# sensor_node.net
KiCad netlist of a schematic drawn in EAGLE
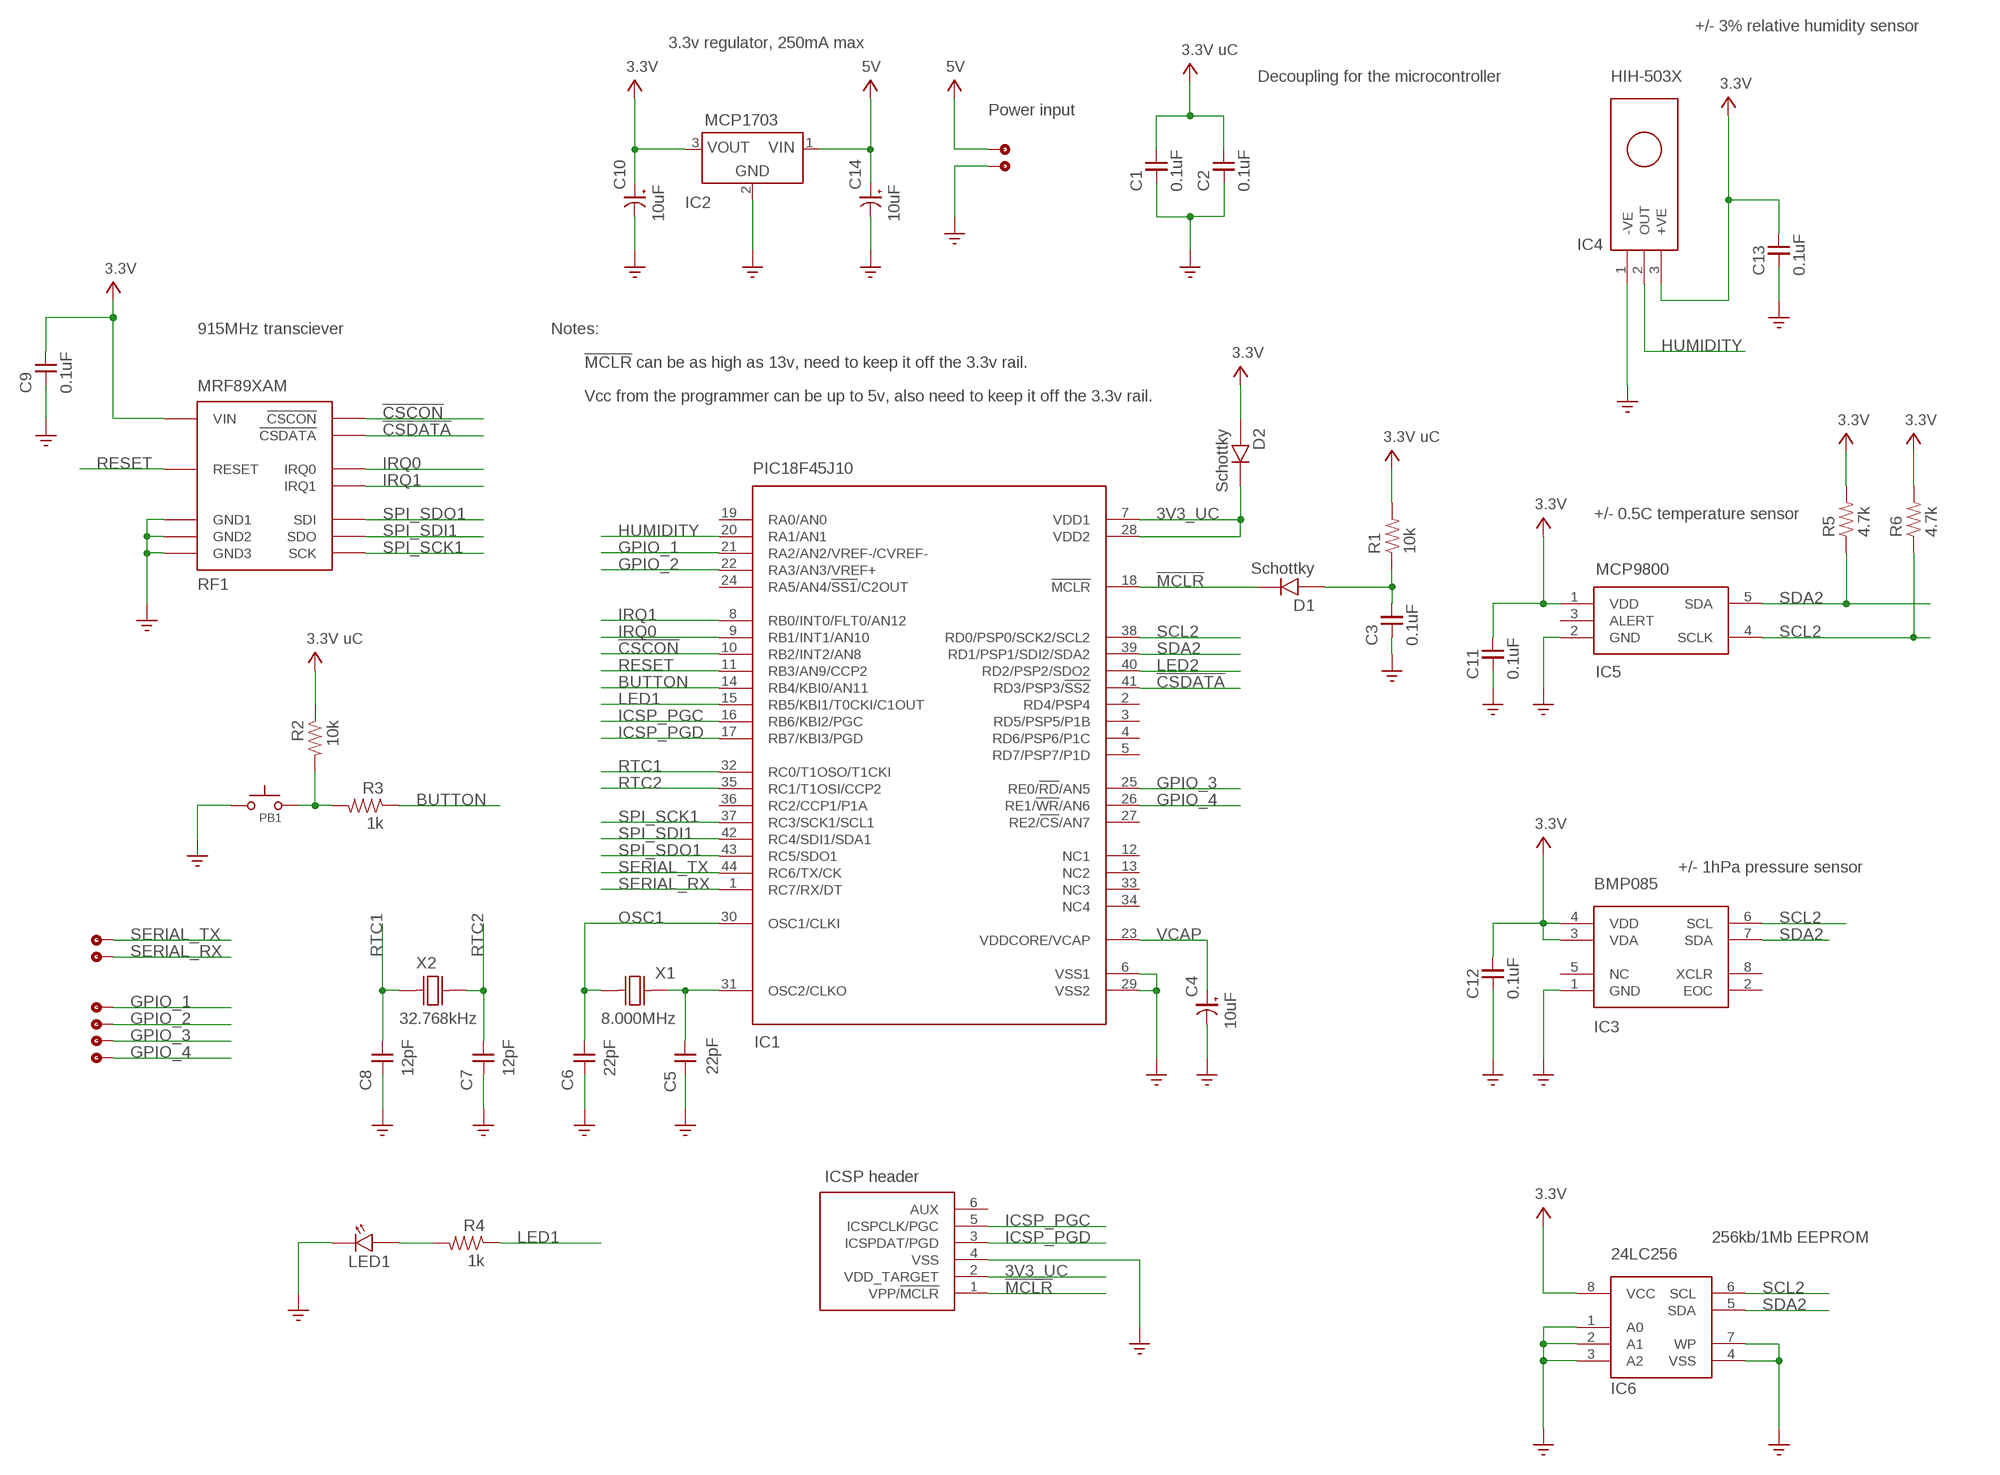
[diagram p0: schematic, sheet 1]

(export (version "E")
  (design (tool "Eeschema 10.0.6"))
  (components
    (comp (ref "C1")
      (value "0.1uF")
      (footprint "eagle-import:0805")
      (libsource (lib "eagle-import") (part "CAPACITOR0805"))
    )
    (comp (ref "C2")
      (value "0.1uF")
      (footprint "eagle-import:0805")
      (libsource (lib "eagle-import") (part "CAPACITOR0805"))
    )
    (comp (ref "C3")
      (value "0.1uF")
      (footprint "eagle-import:0805")
      (libsource (lib "eagle-import") (part "CAPACITOR0805"))
    )
    (comp (ref "C4")
      (value "10uF")
      (footprint "eagle-import:1206")
      (libsource (lib "eagle-import") (part "thomas_july_29_2013_CAPACITOR+"))
    )
    (comp (ref "C5")
      (value "22pF")
      (footprint "eagle-import:0805")
      (libsource (lib "eagle-import") (part "CAPACITOR0805"))
    )
    (comp (ref "C6")
      (value "22pF")
      (footprint "eagle-import:0805")
      (libsource (lib "eagle-import") (part "CAPACITOR0805"))
    )
    (comp (ref "C7")
      (value "12pF")
      (footprint "eagle-import:0805")
      (libsource (lib "eagle-import") (part "CAPACITOR0805"))
    )
    (comp (ref "C8")
      (value "12pF")
      (footprint "eagle-import:0805")
      (libsource (lib "eagle-import") (part "CAPACITOR0805"))
    )
    (comp (ref "C9")
      (value "0.1uF")
      (footprint "eagle-import:0805")
      (libsource (lib "eagle-import") (part "CAPACITOR0805"))
    )
    (comp (ref "C10")
      (value "10uF")
      (footprint "eagle-import:1206")
      (libsource (lib "eagle-import") (part "CAPACITOR+"))
    )
    (comp (ref "C11")
      (value "0.1uF")
      (footprint "eagle-import:0805")
      (libsource (lib "eagle-import") (part "CAPACITOR0805"))
    )
    (comp (ref "C12")
      (value "0.1uF")
      (footprint "eagle-import:0805")
      (libsource (lib "eagle-import") (part "CAPACITOR0805"))
    )
    (comp (ref "C13")
      (value "0.1uF")
      (footprint "eagle-import:0805")
      (libsource (lib "eagle-import") (part "CAPACITOR0805"))
    )
    (comp (ref "C14")
      (value "10uF")
      (footprint "eagle-import:1206")
      (libsource (lib "eagle-import") (part "CAPACITOR+"))
    )
    (comp (ref "CONN1")
      (value "ICSP header")
      (footprint "eagle-import:ISP_HEADER")
      (libsource (lib "eagle-import") (part "ICSP_HEADER_2X6"))
    )
    (comp (ref "D1")
      (value "Schottky")
      (footprint "eagle-import:0805")
      (libsource (lib "eagle-import") (part "DIODE0805"))
    )
    (comp (ref "D2")
      (value "Schottky")
      (footprint "eagle-import:0805")
      (libsource (lib "eagle-import") (part "DIODE0805"))
    )
    (comp (ref "IC1")
      (value "PIC18F45J10")
      (footprint "eagle-import:TQFP_44")
      (libsource (lib "eagle-import") (part "PIC18F45J10"))
    )
    (comp (ref "IC2")
      (value "MCP1703")
      (footprint "eagle-import:SOT-23A")
      (libsource (lib "eagle-import") (part "MCP1703"))
    )
    (comp (ref "IC3")
      (value "BMP085")
      (footprint "eagle-import:LCC8")
      (libsource (lib "eagle-import") (part "BMP085"))
    )
    (comp (ref "IC4")
      (value "HIH-503X")
      (footprint "eagle-import:HIH_503X")
      (libsource (lib "eagle-import") (part "HIH-503X"))
    )
    (comp (ref "IC5")
      (value "MCP9800")
      (footprint "eagle-import:SOT_23-5")
      (libsource (lib "eagle-import") (part "MCP9800"))
    )
    (comp (ref "IC6")
      (value "24LC256")
      (footprint "eagle-import:SO_8")
      (libsource (lib "eagle-import") (part "MCP24LC256_SOIC"))
    )
    (comp (ref "LED1")
      (value "LED0805")
      (footprint "eagle-import:0805")
      (libsource (lib "eagle-import") (part "LED0805"))
    )
    (comp (ref "PB1")
      (value "BUTTON_2PADS")
      (footprint "eagle-import:BUTTON_4SMD")
      (libsource (lib "eagle-import") (part "BUTTON_2PADS"))
    )
    (comp (ref "R1")
      (value "10k")
      (footprint "eagle-import:0805")
      (libsource (lib "eagle-import") (part "RESISTOR0805SMD"))
    )
    (comp (ref "R2")
      (value "10k")
      (footprint "eagle-import:0805")
      (libsource (lib "eagle-import") (part "RESISTOR0805SMD"))
    )
    (comp (ref "R3")
      (value "1k")
      (footprint "eagle-import:0805")
      (libsource (lib "eagle-import") (part "RESISTOR0805SMD"))
    )
    (comp (ref "R4")
      (value "1k")
      (footprint "eagle-import:0805")
      (libsource (lib "eagle-import") (part "RESISTOR0805SMD"))
    )
    (comp (ref "R5")
      (value "4.7k")
      (footprint "eagle-import:0805")
      (libsource (lib "eagle-import") (part "RESISTOR0805SMD"))
    )
    (comp (ref "R6")
      (value "4.7k")
      (footprint "eagle-import:0805")
      (libsource (lib "eagle-import") (part "RESISTOR0805SMD"))
    )
    (comp (ref "RF1")
      (value "MRF89XAM")
      (footprint "eagle-import:MRF89XAM")
      (libsource (lib "eagle-import") (part "MRF89XAM"))
    )
    (comp (ref "TP1") (value "TP") (footprint "eagle-import:TP") (libsource (lib "eagle-import") (part "TP")))
    (comp (ref "TP2") (value "TP") (footprint "eagle-import:TP") (libsource (lib "eagle-import") (part "TP")))
    (comp (ref "TP3") (value "TP") (footprint "eagle-import:TP") (libsource (lib "eagle-import") (part "TP")))
    (comp (ref "TP4") (value "TP") (footprint "eagle-import:TP") (libsource (lib "eagle-import") (part "TP")))
    (comp (ref "TP5") (value "TP") (footprint "eagle-import:TP") (libsource (lib "eagle-import") (part "TP")))
    (comp (ref "TP6") (value "TP") (footprint "eagle-import:TP") (libsource (lib "eagle-import") (part "TP")))
    (comp (ref "TP7") (value "TP") (footprint "eagle-import:TP") (libsource (lib "eagle-import") (part "TP")))
    (comp (ref "TP8") (value "TP") (footprint "eagle-import:TP") (libsource (lib "eagle-import") (part "TP")))
    (comp (ref "X1")
      (value "8.000MHz")
      (footprint "eagle-import:NX5032")
      (libsource (lib "eagle-import") (part "CRYSTALNX5032"))
    )
    (comp (ref "X2")
      (value "32.768kHz")
      (footprint "eagle-import:CM200C")
      (libsource (lib "eagle-import") (part "CRYSTAL"))
    )
  )
  (nets
    (net (code "1") (name "/BUTTON") (class "Default")
      (node (ref "IC1") (pin "14") (pinfunction "RB4/KBI0/AN11_14") (pintype "bidirectional"))
      (node (ref "R3") (pin "1") (pinfunction "1_1") (pintype "passive"))
    )
    (net (code "2") (name "/GPIO_1") (class "Default")
      (node (ref "IC1") (pin "21") (pinfunction "RA2/AN2/VREF-/CVREF-_21") (pintype "bidirectional"))
      (node (ref "TP6") (pin "P$1") (pinfunction "P$1_P$1") (pintype "bidirectional"))
    )
    (net (code "3") (name "/GPIO_2") (class "Default")
      (node (ref "IC1") (pin "22") (pinfunction "RA3/AN3/VREF+_22") (pintype "bidirectional"))
      (node (ref "TP5") (pin "P$1") (pinfunction "P$1_P$1") (pintype "bidirectional"))
    )
    (net (code "4") (name "/GPIO_3") (class "Default")
      (node (ref "IC1") (pin "25") (pinfunction "RE0/~{RD}/AN5_25") (pintype "bidirectional"))
      (node (ref "TP7") (pin "P$1") (pinfunction "P$1_P$1") (pintype "bidirectional"))
    )
    (net (code "5") (name "/GPIO_4") (class "Default")
      (node (ref "IC1") (pin "26") (pinfunction "RE1/~{WR}/AN6_26") (pintype "bidirectional"))
      (node (ref "TP8") (pin "P$1") (pinfunction "P$1_P$1") (pintype "bidirectional"))
    )
    (net (code "6") (name "/HUMIDITY") (class "Default")
      (node (ref "IC1") (pin "20") (pinfunction "RA1/AN1_20") (pintype "bidirectional"))
      (node (ref "IC4") (pin "2") (pinfunction "OUT_2") (pintype "bidirectional"))
    )
    (net (code "7") (name "/ICSP_PGC") (class "Default")
      (node (ref "CONN1") (pin "5") (pinfunction "ICSPCLK/PGC_5") (pintype "bidirectional"))
      (node (ref "IC1") (pin "16") (pinfunction "RB6/KBI2/PGC_16") (pintype "bidirectional"))
    )
    (net (code "8") (name "/ICSP_PGD") (class "Default")
      (node (ref "CONN1") (pin "3") (pinfunction "ICSPDAT/PGD_3") (pintype "bidirectional"))
      (node (ref "IC1") (pin "17") (pinfunction "RB7/KBI3/PGD_17") (pintype "bidirectional"))
    )
    (net (code "9") (name "/IRQ0") (class "Default")
      (node (ref "IC1") (pin "9") (pinfunction "RB1/INT1/AN10_9") (pintype "bidirectional"))
      (node (ref "RF1") (pin "IRQ0") (pinfunction "IRQ0_IRQ0") (pintype "bidirectional"))
    )
    (net (code "10") (name "/IRQ1") (class "Default")
      (node (ref "IC1") (pin "8") (pinfunction "RB0/INT0/FLT0/AN12_8") (pintype "bidirectional"))
      (node (ref "RF1") (pin "IRQ1") (pinfunction "IRQ1_IRQ1") (pintype "bidirectional"))
    )
    (net (code "11") (name "/LED1") (class "Default")
      (node (ref "IC1") (pin "15") (pinfunction "RB5/KBI1/T0CKI/C1OUT_15") (pintype "bidirectional"))
      (node (ref "R4") (pin "1") (pinfunction "1_1") (pintype "passive"))
    )
    (net (code "12") (name "/LED2") (class "Default")
      (node (ref "IC1") (pin "40") (pinfunction "RD2/PSP2/SDO2_40") (pintype "bidirectional"))
    )
    (net (code "13") (name "/OSC1") (class "Default")
      (node (ref "C6") (pin "1") (pinfunction "1_1") (pintype "passive"))
      (node (ref "IC1") (pin "30") (pinfunction "OSC1/CLKI_30") (pintype "bidirectional"))
      (node (ref "X1") (pin "P$1") (pinfunction "1_P$1") (pintype "bidirectional"))
    )
    (net (code "14") (name "/RESET") (class "Default")
      (node (ref "IC1") (pin "11") (pinfunction "RB3/AN9/CCP2_11") (pintype "bidirectional"))
      (node (ref "RF1") (pin "RESET") (pinfunction "RESET_RESET") (pintype "bidirectional"))
    )
    (net (code "15") (name "/RTC1") (class "Default")
      (node (ref "C8") (pin "1") (pinfunction "1_1") (pintype "passive"))
      (node (ref "IC1") (pin "32") (pinfunction "RC0/T1OSO/T1CKI_32") (pintype "bidirectional"))
      (node (ref "X2") (pin "OSC2") (pinfunction "2_OSC2") (pintype "bidirectional"))
    )
    (net (code "16") (name "/RTC2") (class "Default")
      (node (ref "C7") (pin "1") (pinfunction "1_1") (pintype "passive"))
      (node (ref "IC1") (pin "35") (pinfunction "RC1/T1OSI/CCP2_35") (pintype "bidirectional"))
      (node (ref "X2") (pin "OSC1") (pinfunction "1_OSC1") (pintype "bidirectional"))
    )
    (net (code "17") (name "/SCL2") (class "Default")
      (node (ref "IC1") (pin "38") (pinfunction "RD0/PSP0/SCK2/SCL2_38") (pintype "bidirectional"))
      (node (ref "IC3") (pin "6") (pinfunction "SCL_6") (pintype "bidirectional"))
      (node (ref "IC5") (pin "4") (pinfunction "SCLK_4") (pintype "bidirectional"))
      (node (ref "IC6") (pin "6") (pinfunction "SCL_6") (pintype "bidirectional"))
      (node (ref "R6") (pin "1") (pinfunction "1_1") (pintype "passive"))
    )
    (net (code "18") (name "/SDA2") (class "Default")
      (node (ref "IC1") (pin "39") (pinfunction "RD1/PSP1/SDI2/SDA2_39") (pintype "bidirectional"))
      (node (ref "IC3") (pin "7") (pinfunction "SDA_7") (pintype "bidirectional"))
      (node (ref "IC5") (pin "5") (pinfunction "SDA_5") (pintype "bidirectional"))
      (node (ref "IC6") (pin "5") (pinfunction "SDA_5") (pintype "bidirectional"))
      (node (ref "R5") (pin "1") (pinfunction "1_1") (pintype "passive"))
    )
    (net (code "19") (name "/SERIAL_RX") (class "Default")
      (node (ref "IC1") (pin "1") (pinfunction "RC7/RX/DT_1") (pintype "bidirectional"))
      (node (ref "TP2") (pin "P$1") (pinfunction "P$1_P$1") (pintype "bidirectional"))
    )
    (net (code "20") (name "/SERIAL_TX") (class "Default")
      (node (ref "IC1") (pin "44") (pinfunction "RC6/TX/CK_44") (pintype "bidirectional"))
      (node (ref "TP1") (pin "P$1") (pinfunction "P$1_P$1") (pintype "bidirectional"))
    )
    (net (code "21") (name "/SPI_SCK1") (class "Default")
      (node (ref "IC1") (pin "37") (pinfunction "RC3/SCK1/SCL1_37") (pintype "bidirectional"))
      (node (ref "RF1") (pin "SCK") (pinfunction "SCK_SCK") (pintype "bidirectional"))
    )
    (net (code "22") (name "/SPI_SDI1") (class "Default")
      (node (ref "IC1") (pin "42") (pinfunction "RC4/SDI1/SDA1_42") (pintype "bidirectional"))
      (node (ref "RF1") (pin "SDO") (pinfunction "SDO_SDO") (pintype "bidirectional"))
    )
    (net (code "23") (name "/SPI_SDO1") (class "Default")
      (node (ref "IC1") (pin "43") (pinfunction "RC5/SDO1_43") (pintype "bidirectional"))
      (node (ref "RF1") (pin "SDI") (pinfunction "SDI_SDI") (pintype "bidirectional"))
    )
    (net (code "24") (name "/VCAP") (class "Default")
      (node (ref "C4") (pin "1") (pinfunction "1_1") (pintype "passive"))
      (node (ref "IC1") (pin "23") (pinfunction "VDDCORE/VCAP_23") (pintype "bidirectional"))
    )
    (net (code "25") (name "/~{CSCON}") (class "Default")
      (node (ref "IC1") (pin "10") (pinfunction "RB2/INT2/AN8_10") (pintype "bidirectional"))
      (node (ref "RF1") (pin "!CSCON") (pinfunction "~{CSCON}_!CSCON") (pintype "bidirectional"))
    )
    (net (code "26") (name "/~{CSDATA}") (class "Default")
      (node (ref "IC1") (pin "41") (pinfunction "RD3/PSP3/~{SS2}_41") (pintype "bidirectional"))
      (node (ref "RF1") (pin "!CSDATA") (pinfunction "~{CSDATA}_!CSDATA") (pintype "bidirectional"))
    )
    (net (code "27") (name "/~{MCLR}") (class "Default")
      (node (ref "CONN1") (pin "1") (pinfunction "VPP/~{MCLR}_1") (pintype "bidirectional"))
      (node (ref "D1") (pin "2") (pinfunction "K_2") (pintype "bidirectional"))
      (node (ref "IC1") (pin "18") (pinfunction "~{MCLR}_18") (pintype "bidirectional"))
    )
    (net (code "28") (name "3.3V") (class "Default")
      (node (ref "C10") (pin "1") (pinfunction "1_1") (pintype "passive"))
      (node (ref "C11") (pin "2") (pinfunction "2_2") (pintype "passive"))
      (node (ref "C12") (pin "2") (pinfunction "2_2") (pintype "passive"))
      (node (ref "C13") (pin "2") (pinfunction "2_2") (pintype "passive"))
      (node (ref "C9") (pin "2") (pinfunction "2_2") (pintype "passive"))
      (node (ref "D2") (pin "1") (pinfunction "A_1") (pintype "bidirectional"))
      (node (ref "IC2") (pin "3") (pinfunction "VOUT_3") (pintype "power_in"))
      (node (ref "IC3") (pin "3") (pinfunction "VDA_3") (pintype "bidirectional"))
      (node (ref "IC3") (pin "4") (pinfunction "VDD_4") (pintype "bidirectional"))
      (node (ref "IC4") (pin "3") (pinfunction "+VE_3") (pintype "bidirectional"))
      (node (ref "IC5") (pin "1") (pinfunction "VDD_1") (pintype "bidirectional"))
      (node (ref "IC6") (pin "8") (pinfunction "VCC_8") (pintype "bidirectional"))
      (node (ref "R5") (pin "2") (pinfunction "2_2") (pintype "passive"))
      (node (ref "R6") (pin "2") (pinfunction "2_2") (pintype "passive"))
      (node (ref "RF1") (pin "VIN") (pinfunction "VIN_VIN") (pintype "bidirectional"))
    )
    (net (code "29") (name "3.3V uC") (class "Default")
      (node (ref "C1") (pin "2") (pinfunction "2_2") (pintype "passive"))
      (node (ref "C2") (pin "2") (pinfunction "2_2") (pintype "passive"))
      (node (ref "CONN1") (pin "2") (pinfunction "VDD_TARGET_2") (pintype "bidirectional"))
      (node (ref "D2") (pin "2") (pinfunction "K_2") (pintype "bidirectional"))
      (node (ref "IC1") (pin "28") (pinfunction "VDD2_28") (pintype "bidirectional"))
      (node (ref "IC1") (pin "7") (pinfunction "VDD1_7") (pintype "bidirectional"))
      (node (ref "R1") (pin "2") (pinfunction "2_2") (pintype "passive"))
      (node (ref "R2") (pin "1") (pinfunction "1_1") (pintype "passive"))
    )
    (net (code "30") (name "5V") (class "Default")
      (node (ref "C14") (pin "1") (pinfunction "1_1") (pintype "passive"))
      (node (ref "IC2") (pin "1") (pinfunction "VIN_1") (pintype "power_in"))
      (node (ref "TP3") (pin "P$1") (pinfunction "P$1_P$1") (pintype "bidirectional"))
    )
    (net (code "31") (name "DGND") (class "Default")
      (node (ref "C1") (pin "1") (pinfunction "1_1") (pintype "passive"))
      (node (ref "C10") (pin "2") (pinfunction "2_2") (pintype "passive"))
      (node (ref "C11") (pin "1") (pinfunction "1_1") (pintype "passive"))
      (node (ref "C12") (pin "1") (pinfunction "1_1") (pintype "passive"))
      (node (ref "C13") (pin "1") (pinfunction "1_1") (pintype "passive"))
      (node (ref "C14") (pin "2") (pinfunction "2_2") (pintype "passive"))
      (node (ref "C2") (pin "1") (pinfunction "1_1") (pintype "passive"))
      (node (ref "C3") (pin "1") (pinfunction "1_1") (pintype "passive"))
      (node (ref "C4") (pin "2") (pinfunction "2_2") (pintype "passive"))
      (node (ref "C5") (pin "2") (pinfunction "2_2") (pintype "passive"))
      (node (ref "C6") (pin "2") (pinfunction "2_2") (pintype "passive"))
      (node (ref "C7") (pin "2") (pinfunction "2_2") (pintype "passive"))
      (node (ref "C8") (pin "2") (pinfunction "2_2") (pintype "passive"))
      (node (ref "C9") (pin "1") (pinfunction "1_1") (pintype "passive"))
      (node (ref "CONN1") (pin "4") (pinfunction "VSS_4") (pintype "bidirectional"))
      (node (ref "IC1") (pin "29") (pinfunction "VSS2_29") (pintype "bidirectional"))
      (node (ref "IC1") (pin "6") (pinfunction "VSS1_6") (pintype "bidirectional"))
      (node (ref "IC2") (pin "2") (pinfunction "GND_2") (pintype "power_in"))
      (node (ref "IC3") (pin "1") (pinfunction "GND_1") (pintype "bidirectional"))
      (node (ref "IC4") (pin "1") (pinfunction "-VE_1") (pintype "bidirectional"))
      (node (ref "IC5") (pin "2") (pinfunction "GND_2") (pintype "bidirectional"))
      (node (ref "IC6") (pin "1") (pinfunction "A0_1") (pintype "bidirectional"))
      (node (ref "IC6") (pin "2") (pinfunction "A1_2") (pintype "bidirectional"))
      (node (ref "IC6") (pin "3") (pinfunction "A2_3") (pintype "bidirectional"))
      (node (ref "IC6") (pin "4") (pinfunction "VSS_4") (pintype "bidirectional"))
      (node (ref "IC6") (pin "7") (pinfunction "WP_7") (pintype "bidirectional"))
      (node (ref "LED1") (pin "2") (pinfunction "K_2") (pintype "bidirectional"))
      (node (ref "PB1") (pin "3") (pinfunction "P$2_3") (pintype "bidirectional"))
      (node (ref "RF1") (pin "GND1") (pinfunction "GND1_GND1") (pintype "bidirectional"))
      (node (ref "RF1") (pin "GND2") (pinfunction "GND2_GND2") (pintype "bidirectional"))
      (node (ref "RF1") (pin "GND3") (pinfunction "GND3_GND3") (pintype "bidirectional"))
      (node (ref "TP4") (pin "P$1") (pinfunction "P$1_P$1") (pintype "bidirectional"))
    )
    (net (code "32") (name "Net-(D1-A)") (class "Default")
      (node (ref "C3") (pin "2") (pinfunction "2_2") (pintype "passive"))
      (node (ref "D1") (pin "1") (pinfunction "A_1") (pintype "bidirectional"))
      (node (ref "R1") (pin "1") (pinfunction "1_1") (pintype "passive"))
    )
    (net (code "33") (name "Net-(IC1-OSC2{slash}CLKO)") (class "Default")
      (node (ref "C5") (pin "1") (pinfunction "1_1") (pintype "passive"))
      (node (ref "IC1") (pin "31") (pinfunction "OSC2/CLKO_31") (pintype "bidirectional"))
      (node (ref "X1") (pin "P$2") (pinfunction "2_P$2") (pintype "bidirectional"))
    )
    (net (code "34") (name "Net-(LED1-A)") (class "Default")
      (node (ref "LED1") (pin "1") (pinfunction "A_1") (pintype "bidirectional"))
      (node (ref "R4") (pin "2") (pinfunction "2_2") (pintype "passive"))
    )
    (net (code "35") (name "Net-(PB1-P$1)") (class "Default")
      (node (ref "PB1") (pin "1") (pinfunction "P$1_1") (pintype "bidirectional"))
      (node (ref "R2") (pin "2") (pinfunction "2_2") (pintype "passive"))
      (node (ref "R3") (pin "2") (pinfunction "2_2") (pintype "passive"))
    )
    (net (code "36") (name "unconnected-(CONN1-AUX-Pad6)") (class "Default")
      (node (ref "CONN1") (pin "6") (pinfunction "AUX_6") (pintype "bidirectional"))
    )
    (net (code "37") (name "unconnected-(IC1-NC1-Pad12)") (class "Default")
      (node (ref "IC1") (pin "12") (pinfunction "NC1_12") (pintype "bidirectional"))
    )
    (net (code "38") (name "unconnected-(IC1-NC2-Pad13)") (class "Default")
      (node (ref "IC1") (pin "13") (pinfunction "NC2_13") (pintype "bidirectional"))
    )
    (net (code "39") (name "unconnected-(IC1-NC3-Pad33)") (class "Default")
      (node (ref "IC1") (pin "33") (pinfunction "NC3_33") (pintype "bidirectional"))
    )
    (net (code "40") (name "unconnected-(IC1-NC4-Pad34)") (class "Default")
      (node (ref "IC1") (pin "34") (pinfunction "NC4_34") (pintype "bidirectional"))
    )
    (net (code "41") (name "unconnected-(IC1-RA0{slash}AN0-Pad19)") (class "Default")
      (node (ref "IC1") (pin "19") (pinfunction "RA0/AN0_19") (pintype "bidirectional"))
    )
    (net (code "42") (name "unconnected-(IC1-RA5{slash}AN4{slash}~{SS1}{slash}C2OUT-Pad24)") (class "Default")
      (node (ref "IC1") (pin "24") (pinfunction "RA5/AN4/~{SS1}/C2OUT_24") (pintype "bidirectional"))
    )
    (net (code "43") (name "unconnected-(IC1-RC2{slash}CCP1{slash}P1A-Pad36)") (class "Default")
      (node (ref "IC1") (pin "36") (pinfunction "RC2/CCP1/P1A_36") (pintype "bidirectional"))
    )
    (net (code "44") (name "unconnected-(IC1-RD4{slash}PSP4-Pad2)") (class "Default")
      (node (ref "IC1") (pin "2") (pinfunction "RD4/PSP4_2") (pintype "bidirectional"))
    )
    (net (code "45") (name "unconnected-(IC1-RD5{slash}PSP5{slash}P1B-Pad3)") (class "Default")
      (node (ref "IC1") (pin "3") (pinfunction "RD5/PSP5/P1B_3") (pintype "bidirectional"))
    )
    (net (code "46") (name "unconnected-(IC1-RD6{slash}PSP6{slash}P1C-Pad4)") (class "Default")
      (node (ref "IC1") (pin "4") (pinfunction "RD6/PSP6/P1C_4") (pintype "bidirectional"))
    )
    (net (code "47") (name "unconnected-(IC1-RD7{slash}PSP7{slash}P1D-Pad5)") (class "Default")
      (node (ref "IC1") (pin "5") (pinfunction "RD7/PSP7/P1D_5") (pintype "bidirectional"))
    )
    (net (code "48") (name "unconnected-(IC1-RE2{slash}~{CS}{slash}AN7-Pad27)") (class "Default")
      (node (ref "IC1") (pin "27") (pinfunction "RE2/~{CS}/AN7_27") (pintype "bidirectional"))
    )
    (net (code "49") (name "unconnected-(IC3-EOC-Pad2)") (class "Default")
      (node (ref "IC3") (pin "2") (pinfunction "EOC_2") (pintype "bidirectional"))
    )
    (net (code "50") (name "unconnected-(IC3-NC-Pad5)") (class "Default")
      (node (ref "IC3") (pin "5") (pinfunction "NC_5") (pintype "bidirectional"))
    )
    (net (code "51") (name "unconnected-(IC3-XCLR-Pad8)") (class "Default")
      (node (ref "IC3") (pin "8") (pinfunction "XCLR_8") (pintype "bidirectional"))
    )
    (net (code "52") (name "unconnected-(IC5-ALERT-Pad3)") (class "Default")
      (node (ref "IC5") (pin "3") (pinfunction "ALERT_3") (pintype "bidirectional"))
    )
  )
)
